# Qwiic_Adaptive_Switch_Output1_1.net
KiCad netlist of a schematic drawn in EAGLE
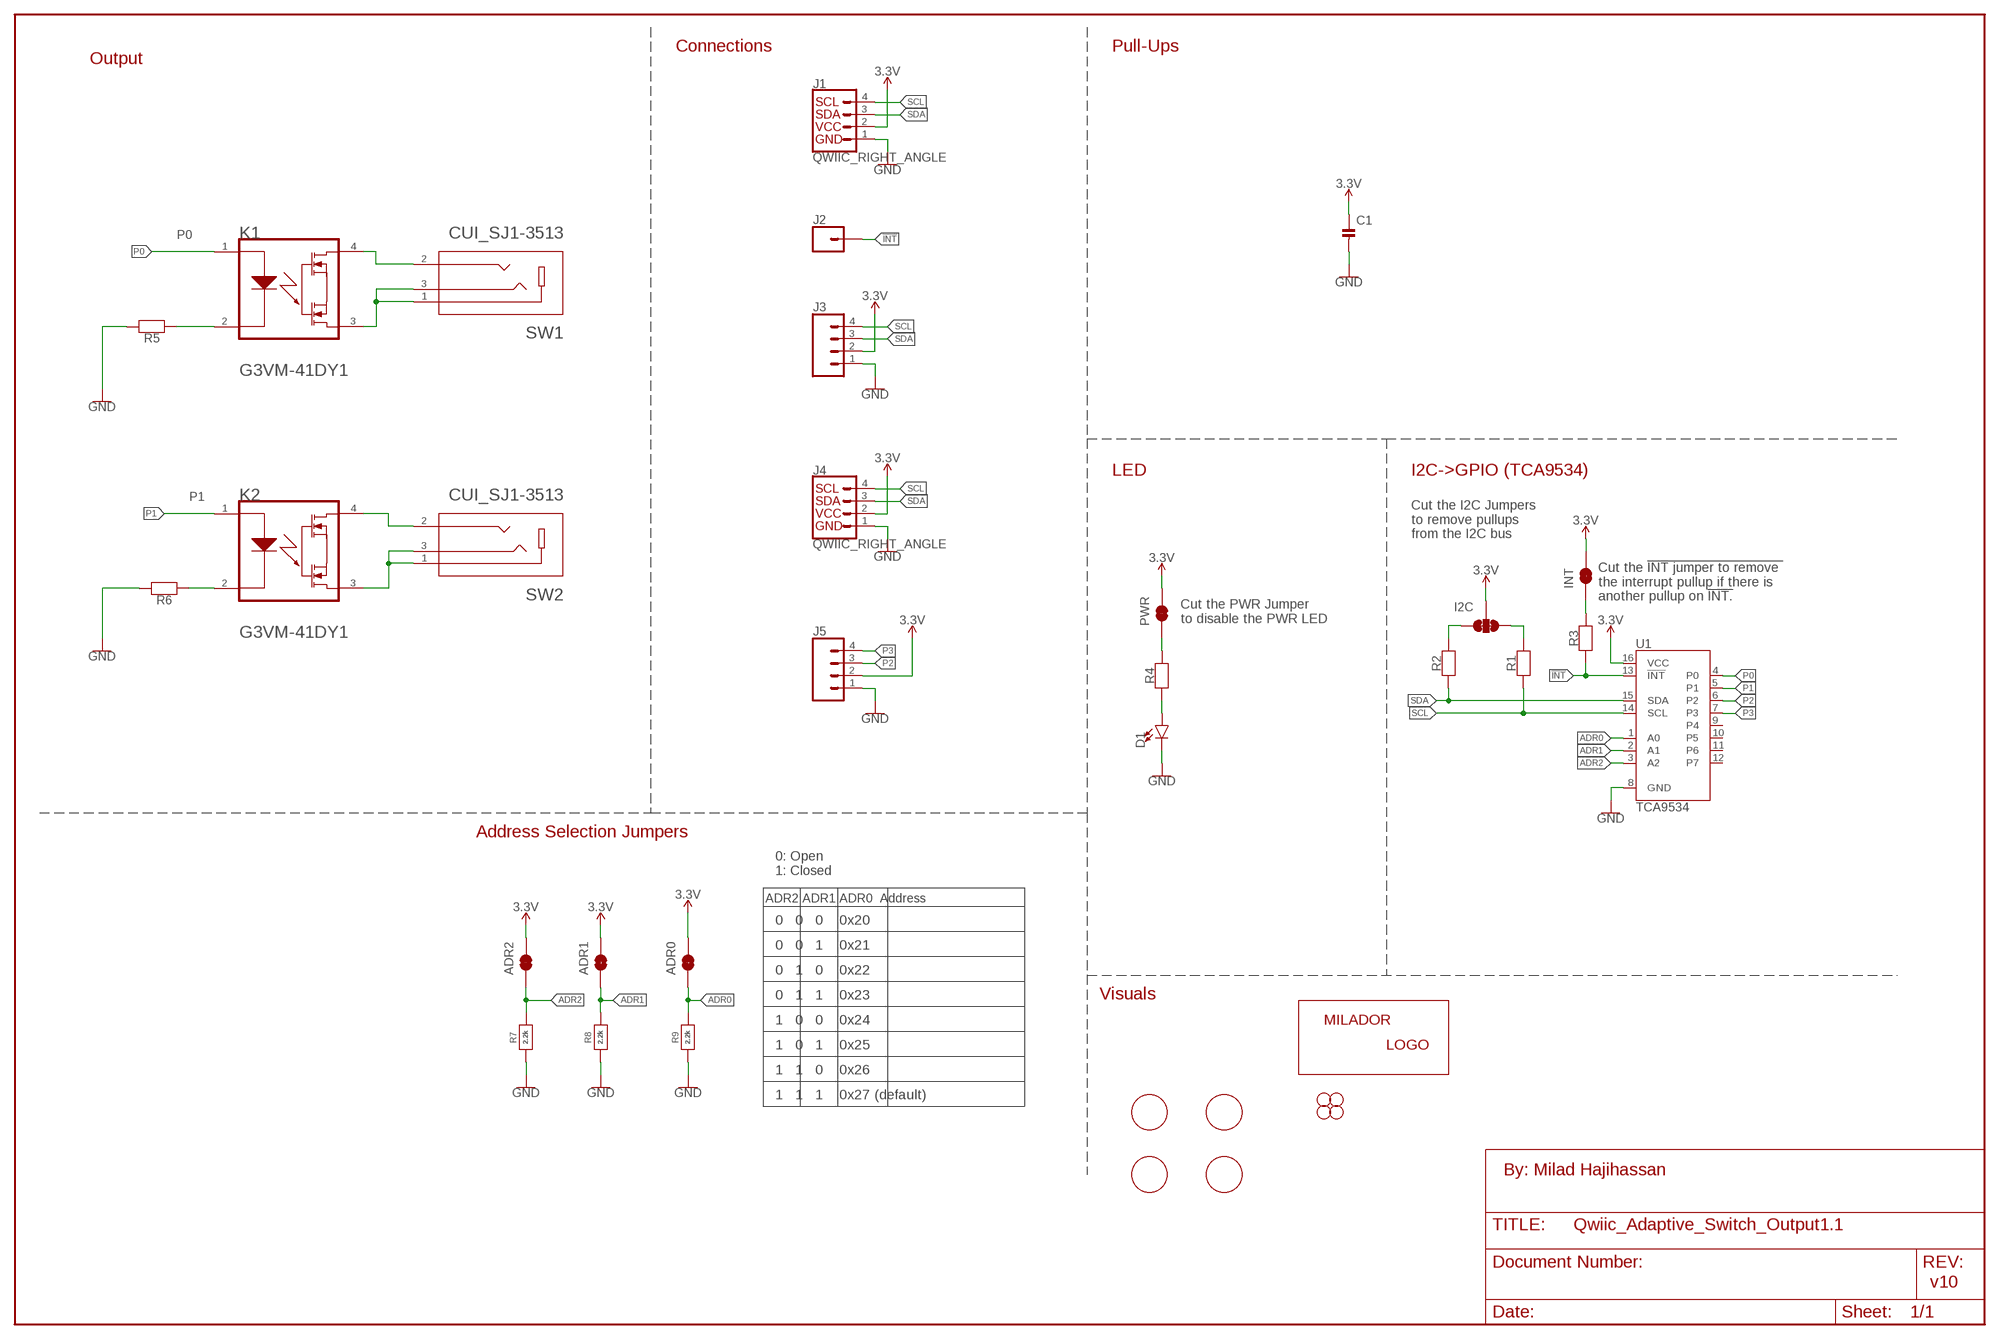
[diagram p0: schematic, sheet 1]

(export (version "E")
  (design (tool "Eeschema 10.0.6"))
  (components
    (comp (ref "ADR0")
      (value "JUMPERS-SMT_2_NC_TRACE_SILK")
      (footprint "eagle-import:JUMPERS_SMT-JUMPER_2_NC_TRACE_SILK")
      (libsource (lib "eagle-import") (part "JUMPERS-SMT_2_NC_TRACE_SILK"))
    )
    (comp (ref "ADR1")
      (value "JUMPERS-SMT_2_NC_TRACE_SILK")
      (footprint "eagle-import:JUMPERS_SMT-JUMPER_2_NC_TRACE_SILK")
      (libsource (lib "eagle-import") (part "JUMPERS-SMT_2_NC_TRACE_SILK"))
    )
    (comp (ref "ADR2")
      (value "JUMPERS-SMT_2_NC_TRACE_SILK")
      (footprint "eagle-import:JUMPERS_SMT-JUMPER_2_NC_TRACE_SILK")
      (libsource (lib "eagle-import") (part "JUMPERS-SMT_2_NC_TRACE_SILK"))
    )
    (comp (ref "C1")
      (value "0.1uF")
      (footprint "eagle-import:0805-MP")
      (libsource (lib "eagle-import") (part "CAP_CERAMIC-0805-MP"))
    )
    (comp (ref "D1")
      (value "RED")
      (footprint "eagle-import:CHIPLED_0805_NOOUTLINE")
      (libsource (lib "eagle-import") (part "LED0805_NOOUTLINE"))
    )
    (comp (ref "H1")
      (value "STAND-OFF-3.3")
      (footprint "eagle-import:STAND-OFF-3.3")
      (libsource (lib "eagle-import") (part "STAND-OFF-3.3"))
    )
    (comp (ref "H2")
      (value "STAND-OFF-3.3")
      (footprint "eagle-import:STAND-OFF-3.3")
      (libsource (lib "eagle-import") (part "STAND-OFF-3.3"))
    )
    (comp (ref "I2C")
      (value "JUMPERS_JUMPER-SMT_3_2-NC_TRACE_SILK")
      (footprint "eagle-import:JUMPERS_SMT-JUMPER_3_2-NC_TRACE_SILK")
      (libsource (lib "eagle-import") (part "JUMPERS_JUMPER-SMT_3_2-NC_TRACE_SILK"))
    )
    (comp (ref "INT")
      (value "JUMPERS-SMT_2_NC_TRACE_SILK")
      (footprint "eagle-import:JUMPERS_SMT-JUMPER_2_NC_TRACE_SILK")
      (libsource (lib "eagle-import") (part "JUMPERS-SMT_2_NC_TRACE_SILK"))
    )
    (comp (ref "J1")
      (value "QWIIC_RIGHT_ANGLE")
      (footprint "eagle-import:CONNECTORS_JST04_1MM_RA")
      (fields (field (name "PROD_ID") "CONN-13694"))
      (libsource (lib "eagle-import") (part "QWIIC_CONNECTORSJS-1MM"))
    )
    (comp (ref "J2")
      (value "CONNECTORS_CONN_01PTH_NO_SILK_YES_STOP")
      (footprint "eagle-import:CONNECTORS_1X01_NO_SILK")
      (libsource (lib "eagle-import") (part "CONNECTORS_CONN_01PTH_NO_SILK_YES_STOP"))
    )
    (comp (ref "J3")
      (value "CONNECTORS_CONN_041X04_NO_SILK")
      (footprint "eagle-import:CONNECTORS_1X04_NO_SILK")
      (libsource (lib "eagle-import") (part "CONNECTORS_CONN_041X04_NO_SILK"))
    )
    (comp (ref "J4")
      (value "QWIIC_RIGHT_ANGLE")
      (footprint "eagle-import:CONNECTORS_JST04_1MM_RA")
      (fields (field (name "PROD_ID") "CONN-13694"))
      (libsource (lib "eagle-import") (part "QWIIC_CONNECTORSJS-1MM"))
    )
    (comp (ref "J5")
      (value "CONNECTORS_CONN_041X04_NO_SILK")
      (footprint "eagle-import:CONNECTORS_1X04_NO_SILK")
      (libsource (lib "eagle-import") (part "CONNECTORS_CONN_041X04_NO_SILK"))
    )
    (comp (ref "JP3")
      (value "STAND-OFF-3.3")
      (footprint "eagle-import:STAND-OFF-3.3")
      (libsource (lib "eagle-import") (part "STAND-OFF-3.3"))
    )
    (comp (ref "JP4")
      (value "STAND-OFF-3.3")
      (footprint "eagle-import:STAND-OFF-3.3")
      (libsource (lib "eagle-import") (part "STAND-OFF-3.3"))
    )
    (comp (ref "K1")
      (value "G3VM-41DY1")
      (footprint "eagle-import:G3VM-41DY1")
      (libsource (lib "eagle-import") (part "G3VM-41DY1"))
    )
    (comp (ref "K2")
      (value "G3VM-41DY1")
      (footprint "eagle-import:G3VM-41DY1")
      (libsource (lib "eagle-import") (part "G3VM-41DY1"))
    )
    (comp (ref "LABEL_2")
      (value "MILADOR-SWITCH-NAME-SW1")
      (footprint "eagle-import:SWITCH-SW1")
      (libsource (lib "eagle-import") (part "MILADOR-SWITCH-NAME-SW1"))
    )
    (comp (ref "LABEL_3")
      (value "MILADOR-SWITCH-NAME-SW2")
      (footprint "eagle-import:SWITCH-SW2")
      (libsource (lib "eagle-import") (part "MILADOR-SWITCH-NAME-SW2"))
    )
    (comp (ref "LABEL_9")
      (value "MILADOR-SWITCH-NAME-SW-OUTPUT")
      (footprint "eagle-import:SWITCH-OUTPUT")
      (libsource (lib "eagle-import") (part "MILADOR-SWITCH-NAME-SW-OUTPUT"))
    )
    (comp (ref "LABEL_13")
      (value "MILADOR-LOGO-")
      (footprint "eagle-import:MILADOR_LOGO1")
      (libsource (lib "eagle-import") (part "MILADOR-LOGO-"))
    )
    (comp (ref "LABEL_18")
      (value "MILADOR-SWITCH-NAME-SW-OUTPUT")
      (footprint "eagle-import:SWITCH-OUTPUT")
      (libsource (lib "eagle-import") (part "MILADOR-SWITCH-NAME-SW-OUTPUT"))
    )
    (comp (ref "PWR")
      (value "JUMPERS-SMT_2_NC_TRACE_SILK")
      (footprint "eagle-import:JUMPERS_SMT-JUMPER_2_NC_TRACE_SILK")
      (libsource (lib "eagle-import") (part "JUMPERS-SMT_2_NC_TRACE_SILK"))
    )
    (comp (ref "R1")
      (value "2.2k")
      (footprint "eagle-import:0805-MP")
      (libsource (lib "eagle-import") (part "RESISTOR-0805-MP"))
    )
    (comp (ref "R2")
      (value "2.2k")
      (footprint "eagle-import:0805-MP")
      (libsource (lib "eagle-import") (part "RESISTOR-0805-MP"))
    )
    (comp (ref "R3")
      (value "10k")
      (footprint "eagle-import:0805-MP")
      (libsource (lib "eagle-import") (part "RESISTOR-0805-MP"))
    )
    (comp (ref "R4")
      (value "1k")
      (footprint "eagle-import:0805-MP")
      (libsource (lib "eagle-import") (part "RESISTOR-0805-MP"))
    )
    (comp (ref "R5")
      (value "220")
      (footprint "eagle-import:0805-MP")
      (libsource (lib "eagle-import") (part "RESISTOR-0805-MP"))
    )
    (comp (ref "R6")
      (value "220")
      (footprint "eagle-import:0805-MP")
      (libsource (lib "eagle-import") (part "RESISTOR-0805-MP"))
    )
    (comp (ref "R7")
      (value "2.2k")
      (footprint "eagle-import:0805-MP")
      (libsource (lib "eagle-import") (part "RESISTOR-0805-MP"))
    )
    (comp (ref "R8")
      (value "2.2k")
      (footprint "eagle-import:0805-MP")
      (libsource (lib "eagle-import") (part "RESISTOR-0805-MP"))
    )
    (comp (ref "R9")
      (value "2.2k")
      (footprint "eagle-import:0805-MP")
      (libsource (lib "eagle-import") (part "RESISTOR-0805-MP"))
    )
    (comp (ref "SW1")
      (value "CUI_SJ1-3513")
      (footprint "eagle-import:CUI_SJ1-3513")
      (libsource (lib "eagle-import") (part "CUI_SJ1-3513"))
    )
    (comp (ref "SW2")
      (value "CUI_SJ1-3513")
      (footprint "eagle-import:CUI_SJ1-3513")
      (libsource (lib "eagle-import") (part "CUI_SJ1-3513"))
    )
    (comp (ref "U1")
      (value "TCA9534")
      (footprint "eagle-import:16SOIC")
      (libsource (lib "eagle-import") (part "TCA9534DWR"))
    )
  )
  (nets
    (net (code "1") (name "/~{INT}") (class "Default")
      (node (ref "J2") (pin "1") (pinfunction "1_1") (pintype "passive"))
      (node (ref "R3") (pin "1") (pinfunction "1_1") (pintype "passive"))
      (node (ref "U1") (pin "13") (pinfunction "~{INT}_13") (pintype "bidirectional"))
    )
    (net (code "2") (name "3.3V") (class "Default")
      (node (ref "ADR0") (pin "2") (pinfunction "2_2") (pintype "passive"))
      (node (ref "ADR1") (pin "2") (pinfunction "2_2") (pintype "passive"))
      (node (ref "ADR2") (pin "2") (pinfunction "2_2") (pintype "passive"))
      (node (ref "C1") (pin "1") (pinfunction "1_1") (pintype "passive"))
      (node (ref "I2C") (pin "2") (pinfunction "2_2") (pintype "passive"))
      (node (ref "INT") (pin "2") (pinfunction "2_2") (pintype "passive"))
      (node (ref "J1") (pin "2") (pinfunction "2_2") (pintype "power_in"))
      (node (ref "J3") (pin "2") (pinfunction "2_2") (pintype "passive"))
      (node (ref "J4") (pin "2") (pinfunction "2_2") (pintype "power_in"))
      (node (ref "J5") (pin "2") (pinfunction "2_2") (pintype "passive"))
      (node (ref "PWR") (pin "2") (pinfunction "2_2") (pintype "passive"))
      (node (ref "U1") (pin "16") (pinfunction "VCC_16") (pintype "bidirectional"))
    )
    (net (code "3") (name "ADR0") (class "Default")
      (node (ref "ADR0") (pin "1") (pinfunction "1_1") (pintype "passive"))
      (node (ref "R9") (pin "2") (pinfunction "2_2") (pintype "passive"))
      (node (ref "U1") (pin "1") (pinfunction "A0_1") (pintype "bidirectional"))
    )
    (net (code "4") (name "ADR1") (class "Default")
      (node (ref "ADR1") (pin "1") (pinfunction "1_1") (pintype "passive"))
      (node (ref "R8") (pin "2") (pinfunction "2_2") (pintype "passive"))
      (node (ref "U1") (pin "2") (pinfunction "A1_2") (pintype "bidirectional"))
    )
    (net (code "5") (name "ADR2") (class "Default")
      (node (ref "ADR2") (pin "1") (pinfunction "1_1") (pintype "passive"))
      (node (ref "R7") (pin "2") (pinfunction "2_2") (pintype "passive"))
      (node (ref "U1") (pin "3") (pinfunction "A2_3") (pintype "bidirectional"))
    )
    (net (code "6") (name "GND") (class "Default")
      (node (ref "C1") (pin "2") (pinfunction "2_2") (pintype "passive"))
      (node (ref "D1") (pin "C") (pinfunction "C_C") (pintype "passive"))
      (node (ref "J1") (pin "1") (pinfunction "1_1") (pintype "power_in"))
      (node (ref "J3") (pin "1") (pinfunction "1_1") (pintype "passive"))
      (node (ref "J4") (pin "1") (pinfunction "1_1") (pintype "power_in"))
      (node (ref "J5") (pin "1") (pinfunction "1_1") (pintype "passive"))
      (node (ref "R5") (pin "2") (pinfunction "2_2") (pintype "passive"))
      (node (ref "R6") (pin "2") (pinfunction "2_2") (pintype "passive"))
      (node (ref "R7") (pin "1") (pinfunction "1_1") (pintype "passive"))
      (node (ref "R8") (pin "1") (pinfunction "1_1") (pintype "passive"))
      (node (ref "R9") (pin "1") (pinfunction "1_1") (pintype "passive"))
      (node (ref "U1") (pin "8") (pinfunction "GND_8") (pintype "bidirectional"))
    )
    (net (code "7") (name "Net-(D1-PadA)") (class "Default")
      (node (ref "D1") (pin "A") (pinfunction "A_A") (pintype "passive"))
      (node (ref "R4") (pin "1") (pinfunction "1_1") (pintype "passive"))
    )
    (net (code "8") (name "Net-(I2C-Pad1)") (class "Default")
      (node (ref "I2C") (pin "1") (pinfunction "1_1") (pintype "passive"))
      (node (ref "R2") (pin "2") (pinfunction "2_2") (pintype "passive"))
    )
    (net (code "9") (name "Net-(I2C-Pad3)") (class "Default")
      (node (ref "I2C") (pin "3") (pinfunction "3_3") (pintype "passive"))
      (node (ref "R1") (pin "2") (pinfunction "2_2") (pintype "passive"))
    )
    (net (code "10") (name "Net-(INT-Pad1)") (class "Default")
      (node (ref "INT") (pin "1") (pinfunction "1_1") (pintype "passive"))
      (node (ref "R3") (pin "2") (pinfunction "2_2") (pintype "passive"))
    )
    (net (code "11") (name "Net-(K1-Pad2)") (class "Default")
      (node (ref "K1") (pin "2") (pinfunction "2_2") (pintype "passive"))
      (node (ref "R5") (pin "1") (pinfunction "1_1") (pintype "passive"))
    )
    (net (code "12") (name "Net-(K1-Pad3)") (class "Default")
      (node (ref "K1") (pin "3") (pinfunction "3_3") (pintype "passive"))
      (node (ref "SW1") (pin "1") (pinfunction "1_1") (pintype "passive"))
      (node (ref "SW1") (pin "3") (pinfunction "3_3") (pintype "passive"))
    )
    (net (code "13") (name "Net-(K1-Pad4)") (class "Default")
      (node (ref "K1") (pin "4") (pinfunction "4_4") (pintype "passive"))
      (node (ref "SW1") (pin "2") (pinfunction "2_2") (pintype "passive"))
    )
    (net (code "14") (name "Net-(K2-Pad2)") (class "Default")
      (node (ref "K2") (pin "2") (pinfunction "2_2") (pintype "passive"))
      (node (ref "R6") (pin "1") (pinfunction "1_1") (pintype "passive"))
    )
    (net (code "15") (name "Net-(K2-Pad3)") (class "Default")
      (node (ref "K2") (pin "3") (pinfunction "3_3") (pintype "passive"))
      (node (ref "SW2") (pin "1") (pinfunction "1_1") (pintype "passive"))
      (node (ref "SW2") (pin "3") (pinfunction "3_3") (pintype "passive"))
    )
    (net (code "16") (name "Net-(K2-Pad4)") (class "Default")
      (node (ref "K2") (pin "4") (pinfunction "4_4") (pintype "passive"))
      (node (ref "SW2") (pin "2") (pinfunction "2_2") (pintype "passive"))
    )
    (net (code "17") (name "Net-(PWR-Pad1)") (class "Default")
      (node (ref "PWR") (pin "1") (pinfunction "1_1") (pintype "passive"))
      (node (ref "R4") (pin "2") (pinfunction "2_2") (pintype "passive"))
    )
    (net (code "18") (name "P0") (class "Default")
      (node (ref "K1") (pin "1") (pinfunction "1_1") (pintype "passive"))
      (node (ref "U1") (pin "4") (pinfunction "P0_4") (pintype "bidirectional"))
    )
    (net (code "19") (name "P1") (class "Default")
      (node (ref "K2") (pin "1") (pinfunction "1_1") (pintype "passive"))
      (node (ref "U1") (pin "5") (pinfunction "P1_5") (pintype "bidirectional"))
    )
    (net (code "20") (name "P2") (class "Default")
      (node (ref "J5") (pin "3") (pinfunction "3_3") (pintype "passive"))
      (node (ref "U1") (pin "6") (pinfunction "P2_6") (pintype "bidirectional"))
    )
    (net (code "21") (name "P3") (class "Default")
      (node (ref "J5") (pin "4") (pinfunction "4_4") (pintype "passive"))
      (node (ref "U1") (pin "7") (pinfunction "P3_7") (pintype "bidirectional"))
    )
    (net (code "22") (name "SCL") (class "Default")
      (node (ref "J1") (pin "4") (pinfunction "4_4") (pintype "passive"))
      (node (ref "J3") (pin "4") (pinfunction "4_4") (pintype "passive"))
      (node (ref "J4") (pin "4") (pinfunction "4_4") (pintype "passive"))
      (node (ref "R1") (pin "1") (pinfunction "1_1") (pintype "passive"))
      (node (ref "U1") (pin "14") (pinfunction "SCL_14") (pintype "bidirectional"))
    )
    (net (code "23") (name "SDA") (class "Default")
      (node (ref "J1") (pin "3") (pinfunction "3_3") (pintype "passive"))
      (node (ref "J3") (pin "3") (pinfunction "3_3") (pintype "passive"))
      (node (ref "J4") (pin "3") (pinfunction "3_3") (pintype "passive"))
      (node (ref "R2") (pin "1") (pinfunction "1_1") (pintype "passive"))
      (node (ref "U1") (pin "15") (pinfunction "SDA_15") (pintype "bidirectional"))
    )
    (net (code "24") (name "unconnected-(U1-P4-Pad9)") (class "Default")
      (node (ref "U1") (pin "9") (pinfunction "P4_9") (pintype "bidirectional"))
    )
    (net (code "25") (name "unconnected-(U1-P5-Pad10)") (class "Default")
      (node (ref "U1") (pin "10") (pinfunction "P5_10") (pintype "bidirectional"))
    )
    (net (code "26") (name "unconnected-(U1-P6-Pad11)") (class "Default")
      (node (ref "U1") (pin "11") (pinfunction "P6_11") (pintype "bidirectional"))
    )
    (net (code "27") (name "unconnected-(U1-P7-Pad12)") (class "Default")
      (node (ref "U1") (pin "12") (pinfunction "P7_12") (pintype "bidirectional"))
    )
  )
)
